# relay_drivers.net
KiCad netlist of a schematic drawn in Altium Designer
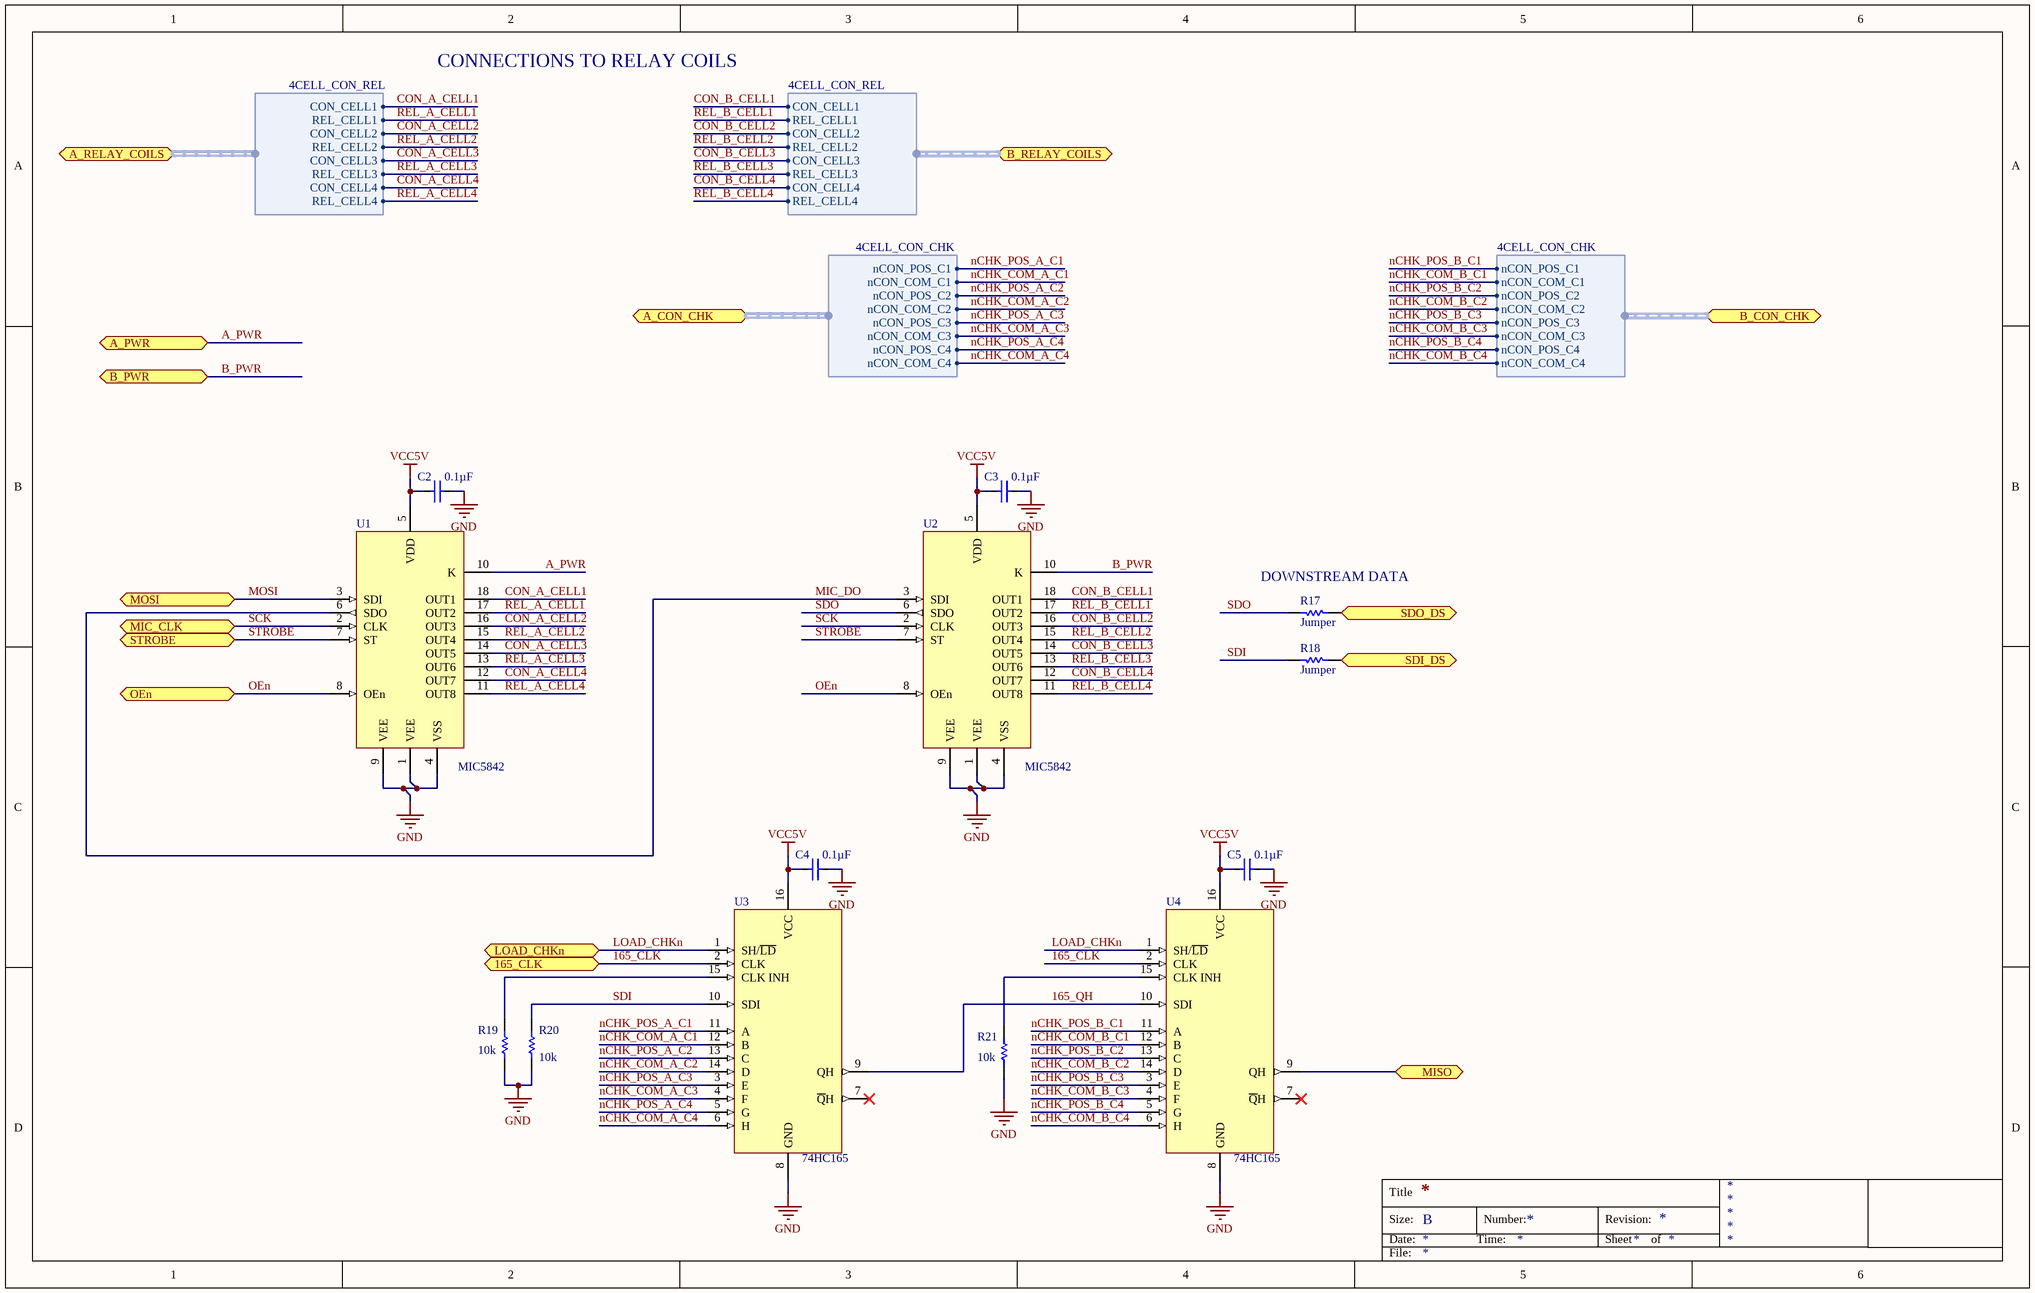
[diagram p0: relay_drivers.SchDoc]

(export (version "E")
  (design (tool "Eeschema 10.0.6"))
  (components
    (comp (ref "C2")
      (value "0.1µF")
      (footprint "CAPC1005X55L25N")
      (description "CAP CER 0.1UF 16V X7R 0402")
      (fields
        (field (name "MANUFACTURER") "Murata Electronics North America")
        (field (name "MANUFACTURER PART NUMBER") "GRM155R71C104JA88D")
      )
      (libsource (lib "mechanart_oshw") (part "CapSMT"))
    )
    (comp (ref "C3")
      (value "0.1µF")
      (footprint "CAPC1005X55L25N")
      (description "CAP CER 0.1UF 16V X7R 0402")
      (fields
        (field (name "MANUFACTURER") "Murata Electronics North America")
        (field (name "MANUFACTURER PART NUMBER") "GRM155R71C104JA88D")
      )
      (libsource (lib "mechanart_oshw") (part "CapSMT"))
    )
    (comp (ref "C4")
      (value "0.1µF")
      (footprint "CAPC1005X55L25N")
      (description "CAP CER 0.1UF 16V X7R 0402")
      (fields
        (field (name "MANUFACTURER") "Murata Electronics North America")
        (field (name "MANUFACTURER PART NUMBER") "GRM155R71C104JA88D")
      )
      (libsource (lib "mechanart_oshw") (part "CapSMT"))
    )
    (comp (ref "C5")
      (value "0.1µF")
      (footprint "CAPC1005X55L25N")
      (description "CAP CER 0.1UF 16V X7R 0402")
      (fields
        (field (name "MANUFACTURER") "Murata Electronics North America")
        (field (name "MANUFACTURER PART NUMBER") "GRM155R71C104JA88D")
      )
      (libsource (lib "mechanart_oshw") (part "CapSMT"))
    )
    (comp (ref "R17")
      (value "Jumper")
      (footprint "RESC_2012[0805]_N")
      (description "RES SMD 0.05 OHM 1% 1/4W 0805")
      (fields
        (field (name "MANUFACTURER") "Vishay Dale")
        (field (name "MANUFACTURER PART NUMBER") "WSL0805R0500FEA18")
      )
      (libsource (lib "mechanart_oshw") (part "ResSMT"))
    )
    (comp (ref "R18")
      (value "Jumper")
      (footprint "RESC_2012[0805]_N")
      (description "RES SMD 0.05 OHM 1% 1/4W 0805")
      (fields
        (field (name "MANUFACTURER") "Vishay Dale")
        (field (name "MANUFACTURER PART NUMBER") "WSL0805R0500FEA18")
      )
      (libsource (lib "mechanart_oshw") (part "ResSMT"))
    )
    (comp (ref "R19")
      (value "10k")
      (footprint "RESC2012X75L55N")
      (description "RES SMD 10K OHM 5% 1/2W 0805")
      (fields
        (field (name "MANUFACTURER") "Panasonic Electronic Components")
        (field (name "MANUFACTURER PART NUMBER") "ERJ-P06J103V")
      )
      (libsource (lib "mechanart_oshw") (part "ResSMT"))
    )
    (comp (ref "R20")
      (value "10k")
      (footprint "RESC2012X75L55N")
      (description "RES SMD 10K OHM 5% 1/2W 0805")
      (fields
        (field (name "MANUFACTURER") "Panasonic Electronic Components")
        (field (name "MANUFACTURER PART NUMBER") "ERJ-P06J103V")
      )
      (libsource (lib "mechanart_oshw") (part "ResSMT"))
    )
    (comp (ref "R21")
      (value "10k")
      (footprint "RESC2012X75L55N")
      (description "RES SMD 10K OHM 5% 1/2W 0805")
      (fields
        (field (name "MANUFACTURER") "Panasonic Electronic Components")
        (field (name "MANUFACTURER PART NUMBER") "ERJ-P06J103V")
      )
      (libsource (lib "mechanart_oshw") (part "ResSMT"))
    )
    (comp (ref "U1")
      (value "MIC5842")
      (footprint "SOIC18P127_1155X1030X265L83X41N")
      (description "IC DRVR LATCH 8BIT SER IN 18SOIC")
      (fields
        (field (name "MANUFACTURER") "Microchip Technology")
        (field (name "MANUFACTURER PART NUMBER") "MIC5842YWM")
      )
      (libsource (lib "mechanart_oshw") (part "MIC584X_18P"))
    )
    (comp (ref "U2")
      (value "MIC5842")
      (footprint "SOIC18P127_1155X1030X265L83X41N")
      (description "IC DRVR LATCH 8BIT SER IN 18SOIC")
      (fields
        (field (name "MANUFACTURER") "Microchip Technology")
        (field (name "MANUFACTURER PART NUMBER") "MIC5842YWM")
      )
      (libsource (lib "mechanart_oshw") (part "MIC584X_18P"))
    )
    (comp (ref "U3")
      (value "74HC165")
      (footprint "SOIC16P127_990X600X175L83X41N")
      (description "IC 8BIT SHIFT REGISTER 16SOIC")
      (fields
        (field (name "MANUFACTURER") "Toshiba Semiconductor and Storage")
        (field (name "MANUFACTURER PART NUMBER") "74HC165D")
      )
      (libsource (lib "mechanart_oshw") (part "74HC165"))
    )
    (comp (ref "U4")
      (value "74HC165")
      (footprint "SOIC16P127_990X600X175L83X41N")
      (description "IC 8BIT SHIFT REGISTER 16SOIC")
      (fields
        (field (name "MANUFACTURER") "Toshiba Semiconductor and Storage")
        (field (name "MANUFACTURER PART NUMBER") "74HC165D")
      )
      (libsource (lib "mechanart_oshw") (part "74HC165"))
    )
  )
  (nets
    (net (code "3") (name "/165_CLK") (class "Default")
      (node (ref "U3") (pin "2") (pinfunction "CLK_2") (pintype "input"))
      (node (ref "U4") (pin "2") (pinfunction "CLK_2") (pintype "input"))
    )
    (net (code "4") (name "/165_QH") (class "Default")
      (node (ref "U3") (pin "9") (pinfunction "QH_9") (pintype "output"))
      (node (ref "U4") (pin "10") (pinfunction "SDI_10") (pintype "input"))
    )
    (net (code "5") (name "/A_PWR") (class "Default")
      (node (ref "U1") (pin "10") (pinfunction "K_10") (pintype "power_in"))
    )
    (net (code "6") (name "/B_PWR") (class "Default")
      (node (ref "U2") (pin "10") (pinfunction "K_10") (pintype "power_in"))
    )
    (net (code "7") (name "/CON_A_CELL1") (class "Default")
      (node (ref "U1") (pin "18") (pinfunction "OUT1_18") (pintype "open_collector"))
    )
    (net (code "8") (name "/CON_A_CELL2") (class "Default")
      (node (ref "U1") (pin "16") (pinfunction "OUT3_16") (pintype "open_collector"))
    )
    (net (code "9") (name "/CON_A_CELL3") (class "Default")
      (node (ref "U1") (pin "14") (pinfunction "OUT5_14") (pintype "open_collector"))
    )
    (net (code "10") (name "/CON_A_CELL4") (class "Default")
      (node (ref "U1") (pin "12") (pinfunction "OUT7_12") (pintype "open_collector"))
    )
    (net (code "11") (name "/CON_B_CELL1") (class "Default")
      (node (ref "U2") (pin "18") (pinfunction "OUT1_18") (pintype "open_collector"))
    )
    (net (code "12") (name "/CON_B_CELL2") (class "Default")
      (node (ref "U2") (pin "16") (pinfunction "OUT3_16") (pintype "open_collector"))
    )
    (net (code "13") (name "/CON_B_CELL3") (class "Default")
      (node (ref "U2") (pin "14") (pinfunction "OUT5_14") (pintype "open_collector"))
    )
    (net (code "14") (name "/CON_B_CELL4") (class "Default")
      (node (ref "U2") (pin "12") (pinfunction "OUT7_12") (pintype "open_collector"))
    )
    (net (code "15") (name "/LOAD_CHKn") (class "Default")
      (node (ref "U3") (pin "1") (pinfunction "SH/~{LD}_1") (pintype "input"))
      (node (ref "U4") (pin "1") (pinfunction "SH/~{LD}_1") (pintype "input"))
    )
    (net (code "16") (name "/MIC_DO") (class "Default")
      (node (ref "U1") (pin "6") (pinfunction "SDO_6") (pintype "output"))
      (node (ref "U2") (pin "3") (pinfunction "SDI_3") (pintype "input"))
    )
    (net (code "17") (name "/MISO") (class "Default")
      (node (ref "U4") (pin "9") (pinfunction "QH_9") (pintype "output"))
    )
    (net (code "18") (name "/MOSI") (class "Default")
      (node (ref "U1") (pin "3") (pinfunction "SDI_3") (pintype "input"))
    )
    (net (code "19") (name "/OEn") (class "Default")
      (node (ref "U1") (pin "8") (pinfunction "OEn_8") (pintype "input"))
      (node (ref "U2") (pin "8") (pinfunction "OEn_8") (pintype "input"))
    )
    (net (code "20") (name "/REL_A_CELL1") (class "Default")
      (node (ref "U1") (pin "17") (pinfunction "OUT2_17") (pintype "open_collector"))
    )
    (net (code "21") (name "/REL_A_CELL2") (class "Default")
      (node (ref "U1") (pin "15") (pinfunction "OUT4_15") (pintype "open_collector"))
    )
    (net (code "22") (name "/REL_A_CELL3") (class "Default")
      (node (ref "U1") (pin "13") (pinfunction "OUT6_13") (pintype "open_collector"))
    )
    (net (code "23") (name "/REL_A_CELL4") (class "Default")
      (node (ref "U1") (pin "11") (pinfunction "OUT8_11") (pintype "open_collector"))
    )
    (net (code "24") (name "/REL_B_CELL1") (class "Default")
      (node (ref "U2") (pin "17") (pinfunction "OUT2_17") (pintype "open_collector"))
    )
    (net (code "25") (name "/REL_B_CELL2") (class "Default")
      (node (ref "U2") (pin "15") (pinfunction "OUT4_15") (pintype "open_collector"))
    )
    (net (code "26") (name "/REL_B_CELL3") (class "Default")
      (node (ref "U2") (pin "13") (pinfunction "OUT6_13") (pintype "open_collector"))
    )
    (net (code "27") (name "/REL_B_CELL4") (class "Default")
      (node (ref "U2") (pin "11") (pinfunction "OUT8_11") (pintype "open_collector"))
    )
    (net (code "28") (name "/SCK") (class "Default")
      (node (ref "U1") (pin "2") (pinfunction "CLK_2") (pintype "input"))
      (node (ref "U2") (pin "2") (pinfunction "CLK_2") (pintype "input"))
    )
    (net (code "29") (name "/SDI") (class "Default")
      (node (ref "R18") (pin "2") (pinfunction "2_2") (pintype "passive"))
      (node (ref "R20") (pin "2") (pinfunction "2_2") (pintype "passive"))
      (node (ref "U3") (pin "10") (pinfunction "SDI_10") (pintype "input"))
    )
    (net (code "30") (name "/SDI_DS") (class "Default")
      (node (ref "R18") (pin "1") (pinfunction "1_1") (pintype "passive"))
    )
    (net (code "31") (name "/SDO") (class "Default")
      (node (ref "R17") (pin "2") (pinfunction "2_2") (pintype "passive"))
      (node (ref "U2") (pin "6") (pinfunction "SDO_6") (pintype "output"))
    )
    (net (code "32") (name "/SDO_DS") (class "Default")
      (node (ref "R17") (pin "1") (pinfunction "1_1") (pintype "passive"))
    )
    (net (code "33") (name "/STROBE") (class "Default")
      (node (ref "U1") (pin "7") (pinfunction "ST_7") (pintype "input"))
      (node (ref "U2") (pin "7") (pinfunction "ST_7") (pintype "input"))
    )
    (net (code "34") (name "/nCHK_COM_A_C1") (class "Default")
      (node (ref "U3") (pin "12") (pinfunction "B_12") (pintype "input"))
    )
    (net (code "35") (name "/nCHK_COM_A_C2") (class "Default")
      (node (ref "U3") (pin "14") (pinfunction "D_14") (pintype "input"))
    )
    (net (code "36") (name "/nCHK_COM_A_C3") (class "Default")
      (node (ref "U3") (pin "4") (pinfunction "F_4") (pintype "input"))
    )
    (net (code "37") (name "/nCHK_COM_A_C4") (class "Default")
      (node (ref "U3") (pin "6") (pinfunction "H_6") (pintype "input"))
    )
    (net (code "38") (name "/nCHK_COM_B_C1") (class "Default")
      (node (ref "U4") (pin "12") (pinfunction "B_12") (pintype "input"))
    )
    (net (code "39") (name "/nCHK_COM_B_C2") (class "Default")
      (node (ref "U4") (pin "14") (pinfunction "D_14") (pintype "input"))
    )
    (net (code "40") (name "/nCHK_COM_B_C3") (class "Default")
      (node (ref "U4") (pin "4") (pinfunction "F_4") (pintype "input"))
    )
    (net (code "41") (name "/nCHK_COM_B_C4") (class "Default")
      (node (ref "U4") (pin "6") (pinfunction "H_6") (pintype "input"))
    )
    (net (code "42") (name "/nCHK_POS_A_C1") (class "Default")
      (node (ref "U3") (pin "11") (pinfunction "A_11") (pintype "input"))
    )
    (net (code "43") (name "/nCHK_POS_A_C2") (class "Default")
      (node (ref "U3") (pin "13") (pinfunction "C_13") (pintype "input"))
    )
    (net (code "44") (name "/nCHK_POS_A_C3") (class "Default")
      (node (ref "U3") (pin "3") (pinfunction "E_3") (pintype "input"))
    )
    (net (code "45") (name "/nCHK_POS_A_C4") (class "Default")
      (node (ref "U3") (pin "5") (pinfunction "G_5") (pintype "input"))
    )
    (net (code "46") (name "/nCHK_POS_B_C1") (class "Default")
      (node (ref "U4") (pin "11") (pinfunction "A_11") (pintype "input"))
    )
    (net (code "47") (name "/nCHK_POS_B_C2") (class "Default")
      (node (ref "U4") (pin "13") (pinfunction "C_13") (pintype "input"))
    )
    (net (code "48") (name "/nCHK_POS_B_C3") (class "Default")
      (node (ref "U4") (pin "3") (pinfunction "E_3") (pintype "input"))
    )
    (net (code "49") (name "/nCHK_POS_B_C4") (class "Default")
      (node (ref "U4") (pin "5") (pinfunction "G_5") (pintype "input"))
    )
    (net (code "52") (name "GND") (class "Default")
      (node (ref "C2") (pin "2") (pinfunction "2_2") (pintype "passive"))
      (node (ref "C3") (pin "2") (pinfunction "2_2") (pintype "passive"))
      (node (ref "C4") (pin "2") (pinfunction "2_2") (pintype "passive"))
      (node (ref "C5") (pin "2") (pinfunction "2_2") (pintype "passive"))
      (node (ref "R19") (pin "1") (pinfunction "1_1") (pintype "passive"))
      (node (ref "R20") (pin "1") (pinfunction "1_1") (pintype "passive"))
      (node (ref "R21") (pin "1") (pinfunction "1_1") (pintype "passive"))
      (node (ref "U1") (pin "1") (pinfunction "VEE_1") (pintype "power_in"))
      (node (ref "U1") (pin "4") (pinfunction "VSS_4") (pintype "power_in"))
      (node (ref "U1") (pin "9") (pinfunction "VEE_9") (pintype "power_in"))
      (node (ref "U2") (pin "1") (pinfunction "VEE_1") (pintype "power_in"))
      (node (ref "U2") (pin "4") (pinfunction "VSS_4") (pintype "power_in"))
      (node (ref "U2") (pin "9") (pinfunction "VEE_9") (pintype "power_in"))
      (node (ref "U3") (pin "8") (pinfunction "GND_8") (pintype "power_in"))
      (node (ref "U4") (pin "8") (pinfunction "GND_8") (pintype "power_in"))
    )
    (net (code "53") (name "Net-(U3-CLK_INH)") (class "Default")
      (node (ref "R19") (pin "2") (pinfunction "2_2") (pintype "passive"))
      (node (ref "U3") (pin "15") (pinfunction "CLK_INH_15") (pintype "input"))
    )
    (net (code "54") (name "Net-(U4-CLK_INH)") (class "Default")
      (node (ref "R21") (pin "2") (pinfunction "2_2") (pintype "passive"))
      (node (ref "U4") (pin "15") (pinfunction "CLK_INH_15") (pintype "input"))
    )
    (net (code "55") (name "VCC5V") (class "Default")
      (node (ref "C2") (pin "1") (pinfunction "1_1") (pintype "passive"))
      (node (ref "C3") (pin "1") (pinfunction "1_1") (pintype "passive"))
      (node (ref "C4") (pin "1") (pinfunction "1_1") (pintype "passive"))
      (node (ref "C5") (pin "1") (pinfunction "1_1") (pintype "passive"))
      (node (ref "U1") (pin "5") (pinfunction "VDD_5") (pintype "power_in"))
      (node (ref "U2") (pin "5") (pinfunction "VDD_5") (pintype "power_in"))
      (node (ref "U3") (pin "16") (pinfunction "VCC_16") (pintype "power_in"))
      (node (ref "U4") (pin "16") (pinfunction "VCC_16") (pintype "power_in"))
    )
    (net (code "56") (name "unconnected-(U3-~{Q}H-Pad7)") (class "Default")
      (node (ref "U3") (pin "7") (pinfunction "~{Q}H_7") (pintype "output+no_connect"))
    )
    (net (code "57") (name "unconnected-(U4-~{Q}H-Pad7)") (class "Default")
      (node (ref "U4") (pin "7") (pinfunction "~{Q}H_7") (pintype "output+no_connect"))
    )
  )
)
